# p2c-002-dx.net
KiCad netlist of a schematic drawn in EAGLE
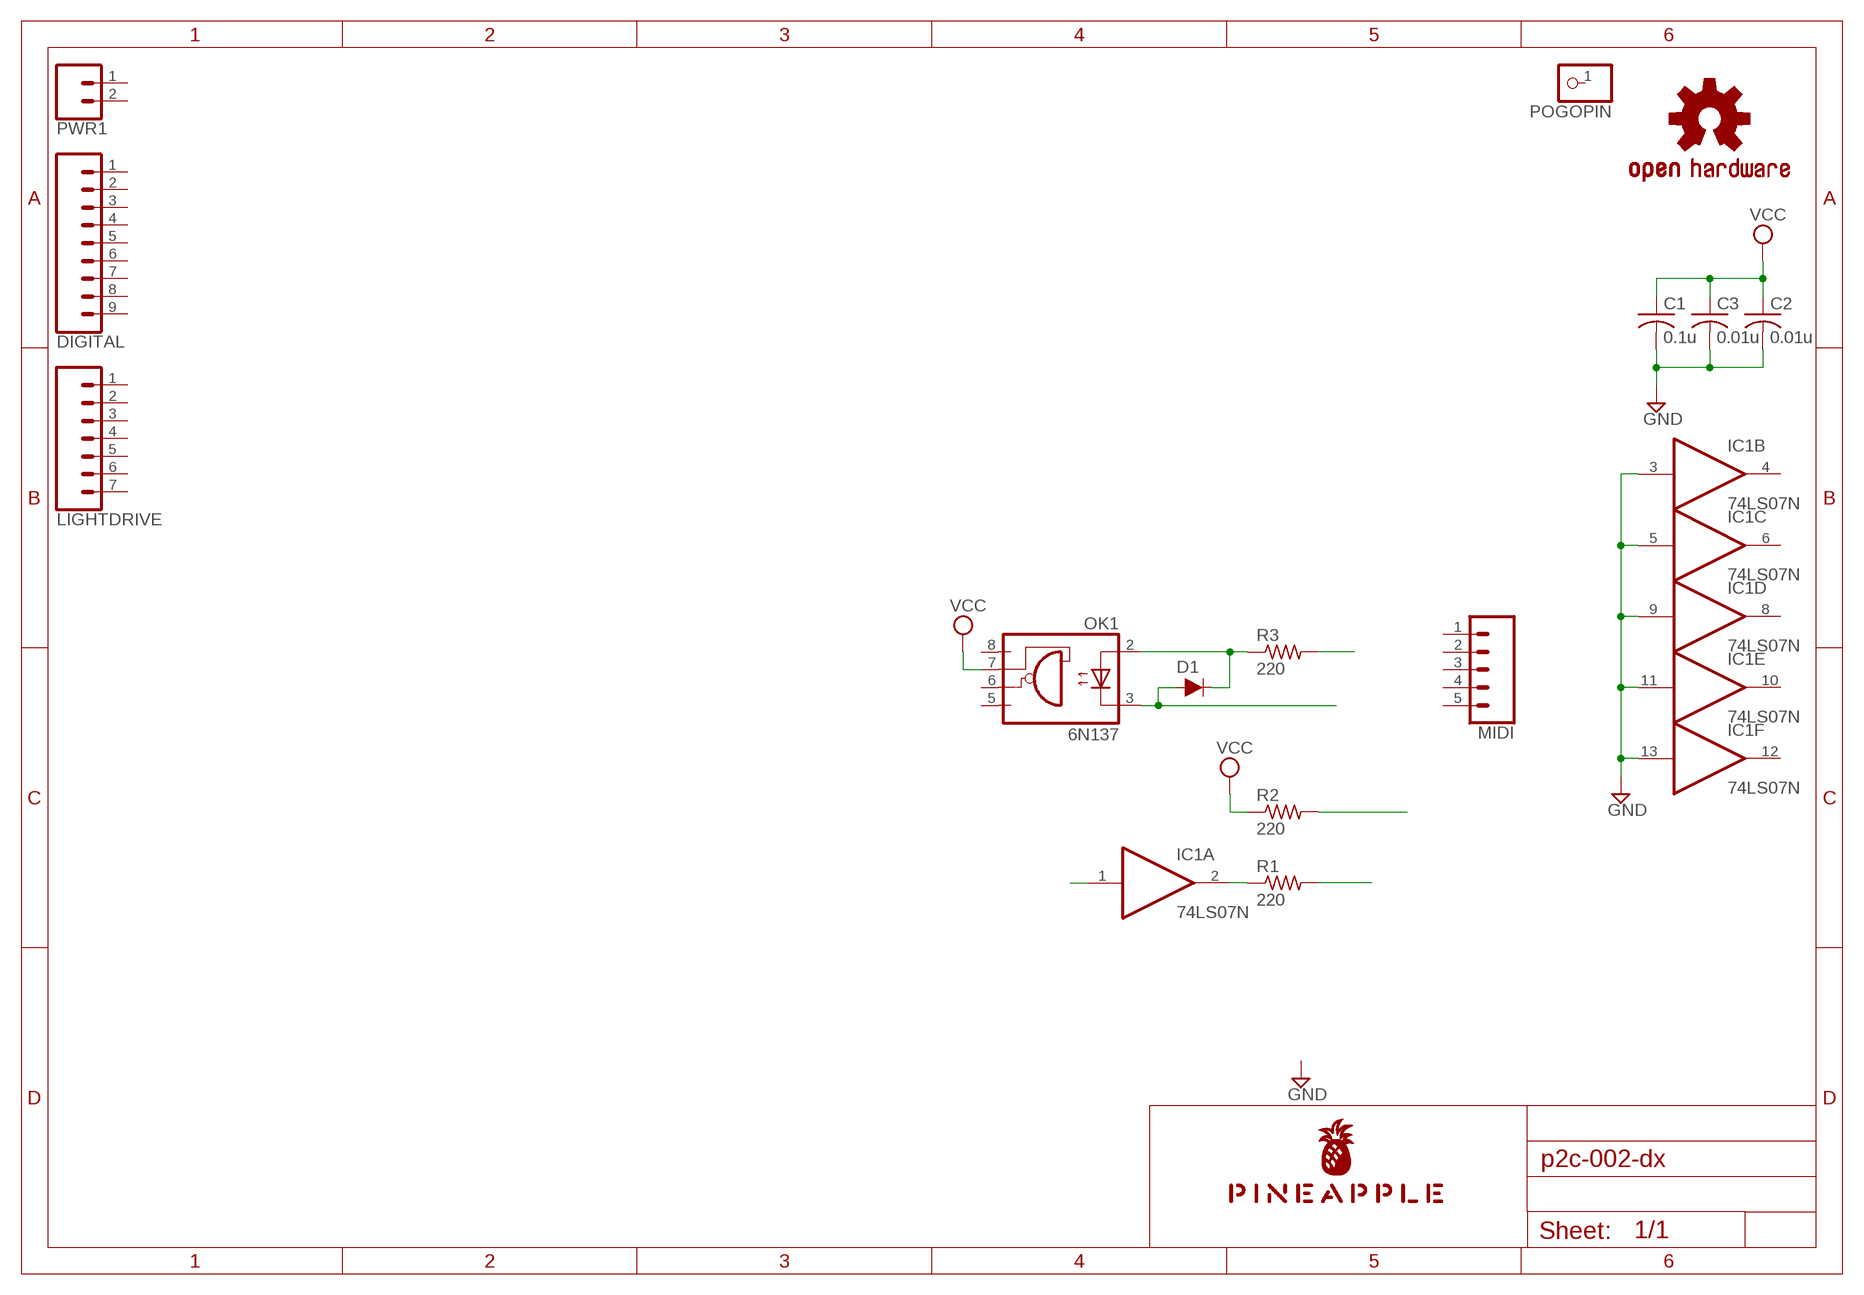
[diagram p0: schematic, sheet 1]

(export (version "E")
  (design (tool "Eeschema 10.0.6"))
  (components
    (comp (ref "C1")
      (value "0.1u")
      (footprint "eagle-import:C025-025X050")
      (libsource (lib "eagle-import") (part "C-US025-025X050"))
    )
    (comp (ref "C2")
      (value "0.01u")
      (footprint "eagle-import:C025-024X044")
      (libsource (lib "eagle-import") (part "C-US025-024X044"))
    )
    (comp (ref "C3")
      (value "0.01u")
      (footprint "eagle-import:C025-024X044")
      (libsource (lib "eagle-import") (part "C-US025-024X044"))
    )
    (comp (ref "D1")
      (value "DIODE-1N4148")
      (footprint "eagle-import:DIODE-1N4148")
      (libsource (lib "eagle-import") (part "DIODE-1N4148"))
    )
    (comp (ref "DIGITAL")
      (value "CONN_09")
      (footprint "eagle-import:1X09")
      (libsource (lib "eagle-import") (part "CONN_09"))
    )
    (comp (ref "IC1")
      (value "74LS07N")
      (footprint "eagle-import:DIL14")
      (libsource (lib "eagle-import") (part "7407NLS"))
    )
    (comp (ref "LIGHTDRIVE")
      (value "CONN_07")
      (footprint "eagle-import:1X07")
      (libsource (lib "eagle-import") (part "CONN_07"))
    )
    (comp (ref "LOGO1")
      (value "OSHW-LOGOS-COPPER")
      (footprint "eagle-import:OSHW-LOGO-S_COPPER")
      (libsource (lib "eagle-import") (part "OSHW-LOGOS-COPPER"))
    )
    (comp (ref "MIDI")
      (value "CONN_05JST")
      (footprint "eagle-import:JST-5-PTH")
      (libsource (lib "eagle-import") (part "CONN_05JST"))
    )
    (comp (ref "OK1")
      (value "6N137")
      (footprint "eagle-import:DIL08")
      (libsource (lib "eagle-import") (part "6N137"))
    )
    (comp (ref "POGOPIN")
      (value "PINHD-1X1")
      (footprint "eagle-import:1X01")
      (libsource (lib "eagle-import") (part "PINHD-1X1"))
    )
    (comp (ref "PWR1")
      (value "CONN_02")
      (footprint "eagle-import:1X02")
      (libsource (lib "eagle-import") (part "CONN_02"))
    )
    (comp (ref "R1")
      (value "220")
      (footprint "eagle-import:0204_5")
      (libsource (lib "eagle-import") (part "R-US_0204/5"))
    )
    (comp (ref "R2")
      (value "220")
      (footprint "eagle-import:0204_5")
      (libsource (lib "eagle-import") (part "R-US_0204/5"))
    )
    (comp (ref "R3")
      (value "220")
      (footprint "eagle-import:0204_5")
      (libsource (lib "eagle-import") (part "R-US_0204/5"))
    )
    (comp (ref "U$1")
      (value "PINEAPPLE450_SILK")
      (footprint "eagle-import:PINEAPPLE450_SILK")
      (libsource (lib "eagle-import") (part "PINEAPPLE450_SILK"))
    )
  )
  (nets
    (net (code "1") (name "GND") (class "Default")
      (node (ref "C1") (pin "2") (pinfunction "2_2") (pintype "passive"))
      (node (ref "C2") (pin "2") (pinfunction "2_2") (pintype "passive"))
      (node (ref "C3") (pin "2") (pinfunction "2_2") (pintype "passive"))
      (node (ref "IC1") (pin "11") (pinfunction "I_11") (pintype "input"))
      (node (ref "IC1") (pin "13") (pinfunction "I_13") (pintype "input"))
      (node (ref "IC1") (pin "3") (pinfunction "I_3") (pintype "input"))
      (node (ref "IC1") (pin "5") (pinfunction "I_5") (pintype "input"))
      (node (ref "IC1") (pin "9") (pinfunction "I_9") (pintype "input"))
    )
    (net (code "2") (name "Net-(IC1A-O)") (class "Default")
      (node (ref "IC1") (pin "2") (pinfunction "O_2") (pintype "open_collector"))
      (node (ref "R1") (pin "1") (pinfunction "1_1") (pintype "passive"))
    )
    (net (code "3") (name "Net-(OK1-A)") (class "Default")
      (node (ref "D1") (pin "C") (pinfunction "C_C") (pintype "passive"))
      (node (ref "OK1") (pin "2") (pinfunction "A_2") (pintype "passive"))
      (node (ref "R3") (pin "1") (pinfunction "1_1") (pintype "passive"))
    )
    (net (code "4") (name "Net-(OK1-C)") (class "Default")
      (node (ref "D1") (pin "A") (pinfunction "A_A") (pintype "passive"))
      (node (ref "OK1") (pin "3") (pinfunction "C_3") (pintype "passive"))
    )
    (net (code "5") (name "VCC") (class "Default")
      (node (ref "C1") (pin "1") (pinfunction "1_1") (pintype "passive"))
      (node (ref "C2") (pin "1") (pinfunction "1_1") (pintype "passive"))
      (node (ref "C3") (pin "1") (pinfunction "1_1") (pintype "passive"))
      (node (ref "OK1") (pin "7") (pinfunction "VE_7") (pintype "passive"))
      (node (ref "R2") (pin "1") (pinfunction "1_1") (pintype "passive"))
    )
    (net (code "6") (name "unconnected-(DIGITAL-Pad1)") (class "Default")
      (node (ref "DIGITAL") (pin "1") (pinfunction "1_1") (pintype "passive"))
    )
    (net (code "7") (name "unconnected-(DIGITAL-Pad2)") (class "Default")
      (node (ref "DIGITAL") (pin "2") (pinfunction "2_2") (pintype "passive"))
    )
    (net (code "8") (name "unconnected-(DIGITAL-Pad3)") (class "Default")
      (node (ref "DIGITAL") (pin "3") (pinfunction "3_3") (pintype "passive"))
    )
    (net (code "9") (name "unconnected-(DIGITAL-Pad4)") (class "Default")
      (node (ref "DIGITAL") (pin "4") (pinfunction "4_4") (pintype "passive"))
    )
    (net (code "10") (name "unconnected-(DIGITAL-Pad5)") (class "Default")
      (node (ref "DIGITAL") (pin "5") (pinfunction "5_5") (pintype "passive"))
    )
    (net (code "11") (name "unconnected-(DIGITAL-Pad6)") (class "Default")
      (node (ref "DIGITAL") (pin "6") (pinfunction "6_6") (pintype "passive"))
    )
    (net (code "12") (name "unconnected-(DIGITAL-Pad7)") (class "Default")
      (node (ref "DIGITAL") (pin "7") (pinfunction "7_7") (pintype "passive"))
    )
    (net (code "13") (name "unconnected-(DIGITAL-Pad8)") (class "Default")
      (node (ref "DIGITAL") (pin "8") (pinfunction "8_8") (pintype "passive"))
    )
    (net (code "14") (name "unconnected-(DIGITAL-Pad9)") (class "Default")
      (node (ref "DIGITAL") (pin "9") (pinfunction "9_9") (pintype "passive"))
    )
    (net (code "15") (name "unconnected-(IC1A-I-Pad1)") (class "Default")
      (node (ref "IC1") (pin "1") (pinfunction "I_1") (pintype "input"))
    )
    (net (code "16") (name "unconnected-(IC1B-O-Pad4)") (class "Default")
      (node (ref "IC1") (pin "4") (pinfunction "O_4") (pintype "open_collector"))
    )
    (net (code "17") (name "unconnected-(IC1C-O-Pad6)") (class "Default")
      (node (ref "IC1") (pin "6") (pinfunction "O_6") (pintype "open_collector"))
    )
    (net (code "18") (name "unconnected-(IC1D-O-Pad8)") (class "Default")
      (node (ref "IC1") (pin "8") (pinfunction "O_8") (pintype "open_collector"))
    )
    (net (code "19") (name "unconnected-(IC1E-O-Pad10)") (class "Default")
      (node (ref "IC1") (pin "10") (pinfunction "O_10") (pintype "open_collector"))
    )
    (net (code "20") (name "unconnected-(IC1F-O-Pad12)") (class "Default")
      (node (ref "IC1") (pin "12") (pinfunction "O_12") (pintype "open_collector"))
    )
    (net (code "21") (name "unconnected-(LIGHTDRIVE-Pad1)") (class "Default")
      (node (ref "LIGHTDRIVE") (pin "1") (pinfunction "1_1") (pintype "passive"))
    )
    (net (code "22") (name "unconnected-(LIGHTDRIVE-Pad2)") (class "Default")
      (node (ref "LIGHTDRIVE") (pin "2") (pinfunction "2_2") (pintype "passive"))
    )
    (net (code "23") (name "unconnected-(LIGHTDRIVE-Pad3)") (class "Default")
      (node (ref "LIGHTDRIVE") (pin "3") (pinfunction "3_3") (pintype "passive"))
    )
    (net (code "24") (name "unconnected-(LIGHTDRIVE-Pad4)") (class "Default")
      (node (ref "LIGHTDRIVE") (pin "4") (pinfunction "4_4") (pintype "passive"))
    )
    (net (code "25") (name "unconnected-(LIGHTDRIVE-Pad5)") (class "Default")
      (node (ref "LIGHTDRIVE") (pin "5") (pinfunction "5_5") (pintype "passive"))
    )
    (net (code "26") (name "unconnected-(LIGHTDRIVE-Pad6)") (class "Default")
      (node (ref "LIGHTDRIVE") (pin "6") (pinfunction "6_6") (pintype "passive"))
    )
    (net (code "27") (name "unconnected-(LIGHTDRIVE-Pad7)") (class "Default")
      (node (ref "LIGHTDRIVE") (pin "7") (pinfunction "7_7") (pintype "passive"))
    )
    (net (code "28") (name "unconnected-(MIDI-Pad1)") (class "Default")
      (node (ref "MIDI") (pin "1") (pinfunction "1_1") (pintype "passive"))
    )
    (net (code "29") (name "unconnected-(MIDI-Pad2)") (class "Default")
      (node (ref "MIDI") (pin "2") (pinfunction "2_2") (pintype "passive"))
    )
    (net (code "30") (name "unconnected-(MIDI-Pad3)") (class "Default")
      (node (ref "MIDI") (pin "3") (pinfunction "3_3") (pintype "passive"))
    )
    (net (code "31") (name "unconnected-(MIDI-Pad4)") (class "Default")
      (node (ref "MIDI") (pin "4") (pinfunction "4_4") (pintype "passive"))
    )
    (net (code "32") (name "unconnected-(MIDI-Pad5)") (class "Default")
      (node (ref "MIDI") (pin "5") (pinfunction "5_5") (pintype "passive"))
    )
    (net (code "33") (name "unconnected-(OK1-GND-Pad5)") (class "Default")
      (node (ref "OK1") (pin "5") (pinfunction "GND_5") (pintype "passive"))
    )
    (net (code "34") (name "unconnected-(OK1-VCC-Pad8)") (class "Default")
      (node (ref "OK1") (pin "8") (pinfunction "VCC_8") (pintype "passive"))
    )
    (net (code "35") (name "unconnected-(OK1-VO-Pad6)") (class "Default")
      (node (ref "OK1") (pin "6") (pinfunction "VO_6") (pintype "passive"))
    )
    (net (code "36") (name "unconnected-(POGOPIN-Pad1)") (class "Default")
      (node (ref "POGOPIN") (pin "1") (pinfunction "1_1") (pintype "passive"))
    )
    (net (code "37") (name "unconnected-(PWR1-Pad1)") (class "Default")
      (node (ref "PWR1") (pin "1") (pinfunction "1_1") (pintype "passive"))
    )
    (net (code "38") (name "unconnected-(PWR1-Pad2)") (class "Default")
      (node (ref "PWR1") (pin "2") (pinfunction "2_2") (pintype "passive"))
    )
    (net (code "39") (name "unconnected-(R1-Pad2)") (class "Default")
      (node (ref "R1") (pin "2") (pinfunction "2_2") (pintype "passive"))
    )
    (net (code "40") (name "unconnected-(R2-Pad2)") (class "Default")
      (node (ref "R2") (pin "2") (pinfunction "2_2") (pintype "passive"))
    )
    (net (code "41") (name "unconnected-(R3-Pad2)") (class "Default")
      (node (ref "R3") (pin "2") (pinfunction "2_2") (pintype "passive"))
    )
  )
)
